# TPS54340_PS_and_Load_Rev1.net
KiCad netlist of a schematic drawn in EAGLE
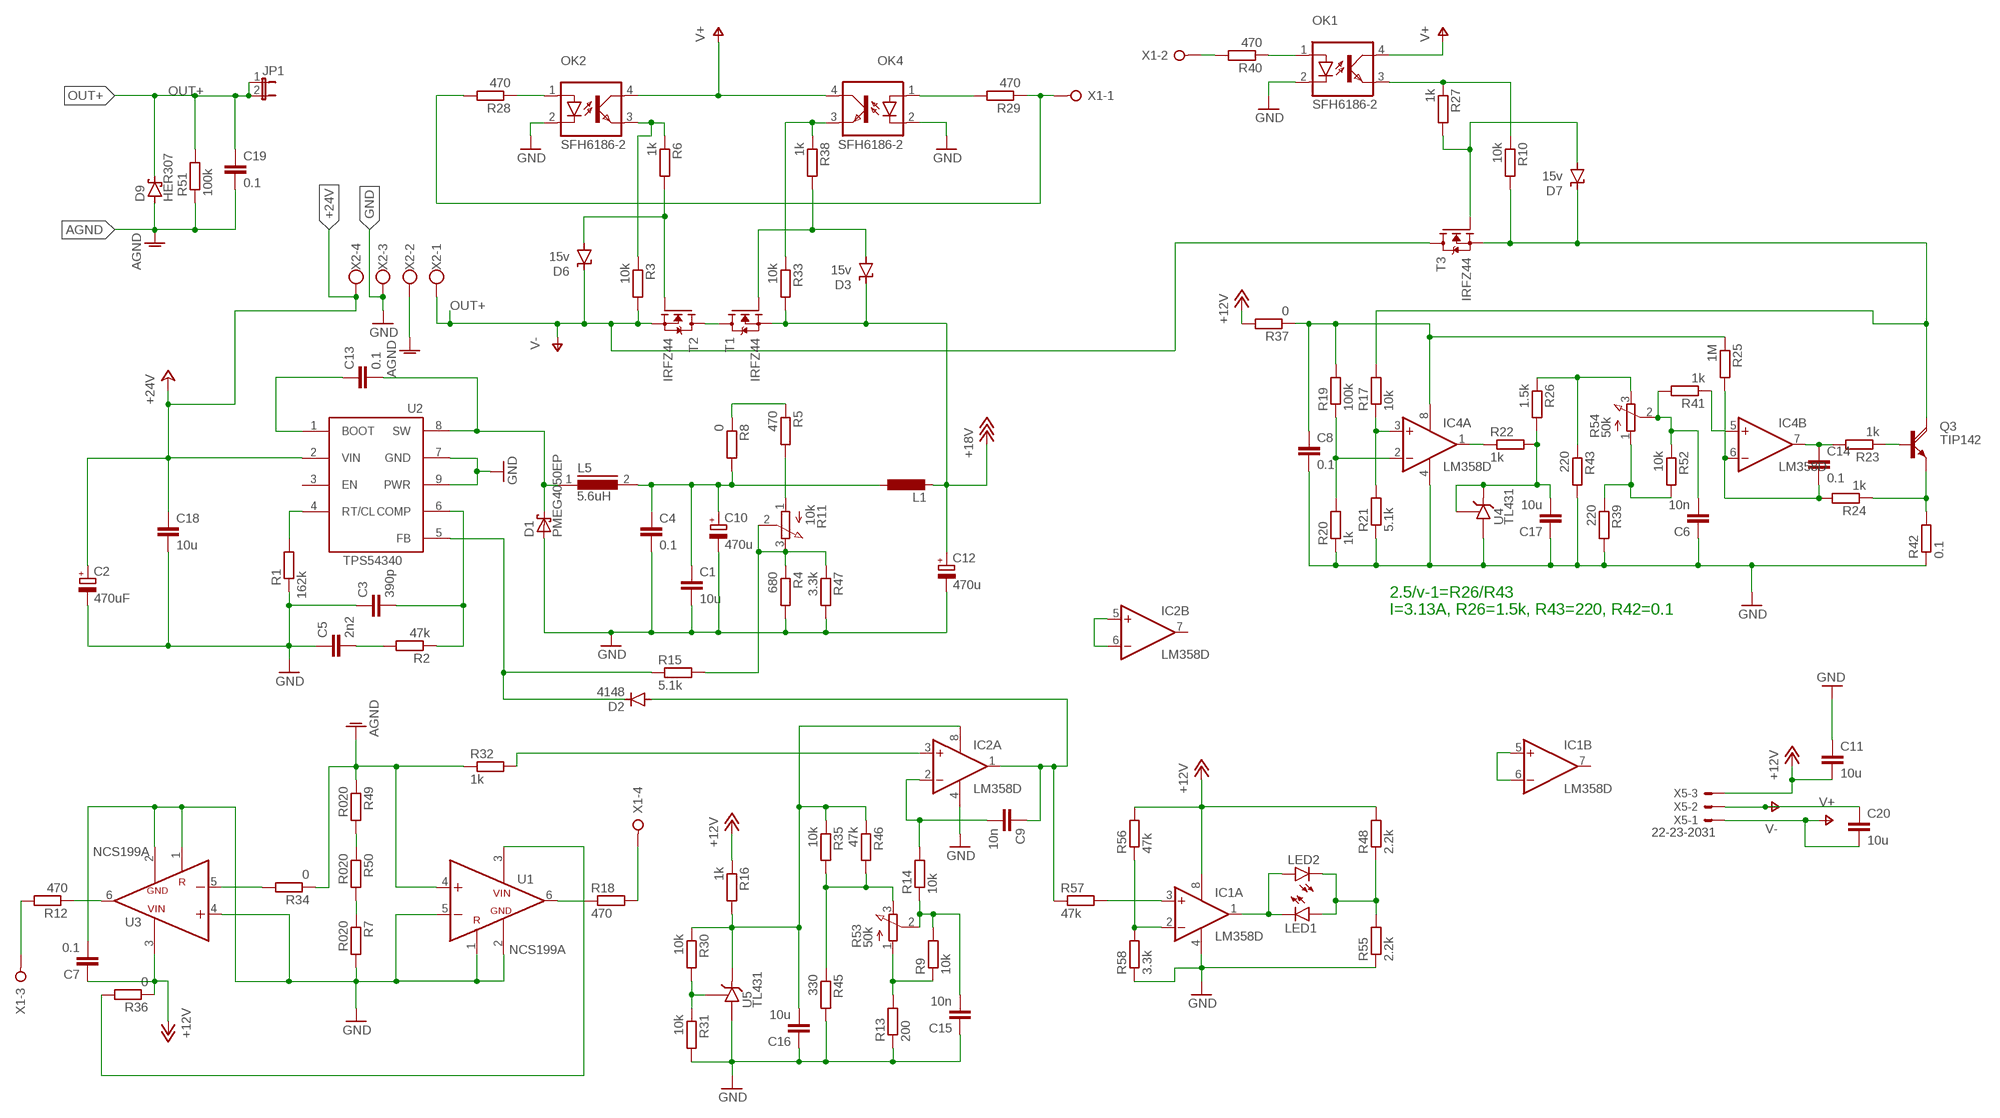
[diagram p0: schematic, sheet 1]

(export (version "E")
  (design (tool "Eeschema 10.0.6"))
  (components
    (comp (ref "C1")
      (value "10u")
      (footprint "eagle-import:C1210")
      (libsource (lib "eagle-import") (part "rcl_334_C-EUC1210"))
    )
    (comp (ref "C2")
      (value "470uF")
      (footprint "eagle-import:E5-10,5")
      (libsource (lib "eagle-import") (part "CPOL-EUE5-10.5"))
    )
    (comp (ref "C3")
      (value "390p")
      (footprint "eagle-import:C0603K")
      (libsource (lib "eagle-import") (part "rcl_334_C-EUC0603K"))
    )
    (comp (ref "C4")
      (value "0.1")
      (footprint "eagle-import:C1206")
      (libsource (lib "eagle-import") (part "C-EUC1206"))
    )
    (comp (ref "C5")
      (value "2n2")
      (footprint "eagle-import:C0603K")
      (libsource (lib "eagle-import") (part "rcl_334_C-EUC0603K"))
    )
    (comp (ref "C6")
      (value "10n")
      (footprint "eagle-import:C0603K")
      (libsource (lib "eagle-import") (part "rcl_334_C-EUC0603K"))
    )
    (comp (ref "C7")
      (value "0.1")
      (footprint "eagle-import:C0603K")
      (libsource (lib "eagle-import") (part "rcl_334_C-EUC0603K"))
    )
    (comp (ref "C8")
      (value "0.1")
      (footprint "eagle-import:C1206")
      (libsource (lib "eagle-import") (part "C-EUC1206"))
    )
    (comp (ref "C9")
      (value "10n")
      (footprint "eagle-import:C0603K")
      (libsource (lib "eagle-import") (part "rcl_334_C-EUC0603K"))
    )
    (comp (ref "C10")
      (value "470u")
      (footprint "eagle-import:E5-10,5")
      (libsource (lib "eagle-import") (part "CPOL-EUE5-10.5"))
    )
    (comp (ref "C11")
      (value "10u")
      (footprint "eagle-import:C1206")
      (libsource (lib "eagle-import") (part "C-EUC1206"))
    )
    (comp (ref "C12")
      (value "470u")
      (footprint "eagle-import:E5-10,5")
      (libsource (lib "eagle-import") (part "CPOL-EUE5-10.5"))
    )
    (comp (ref "C13")
      (value "0.1")
      (footprint "eagle-import:C102-043X133")
      (libsource (lib "eagle-import") (part "rcl_334_C-EU102-043X133"))
    )
    (comp (ref "C14")
      (value "0.1")
      (footprint "eagle-import:C1206")
      (libsource (lib "eagle-import") (part "C-EUC1206"))
    )
    (comp (ref "C15")
      (value "10n")
      (footprint "eagle-import:C0603K")
      (libsource (lib "eagle-import") (part "rcl_334_C-EUC0603K"))
    )
    (comp (ref "C16")
      (value "10u")
      (footprint "eagle-import:C0603K")
      (libsource (lib "eagle-import") (part "rcl_334_C-EUC0603K"))
    )
    (comp (ref "C17")
      (value "10u")
      (footprint "eagle-import:C0603K")
      (libsource (lib "eagle-import") (part "rcl_334_C-EUC0603K"))
    )
    (comp (ref "C18")
      (value "10u")
      (footprint "eagle-import:C1210")
      (libsource (lib "eagle-import") (part "rcl_334_C-EUC1210"))
    )
    (comp (ref "C19")
      (value "0.1")
      (footprint "eagle-import:C150-054X183")
      (libsource (lib "eagle-import") (part "rcl_334_C-EU150-054X183"))
    )
    (comp (ref "C20")
      (value "10u")
      (footprint "eagle-import:C1206")
      (libsource (lib "eagle-import") (part "C-EUC1206"))
    )
    (comp (ref "D1")
      (value "PMEG4050EP")
      (footprint "eagle-import:SOD128")
      (libsource (lib "eagle-import") (part "PMEG4050EP"))
    )
    (comp (ref "D2")
      (value "4148")
      (footprint "eagle-import:SOD80C")
      (libsource (lib "eagle-import") (part "PMLL41SOD80C"))
    )
    (comp (ref "D3")
      (value "15v")
      (footprint "eagle-import:SMBJ")
      (libsource (lib "eagle-import") (part "SUPPRESSOR-SMBJ"))
    )
    (comp (ref "D6")
      (value "15v")
      (footprint "eagle-import:SMBJ")
      (libsource (lib "eagle-import") (part "SUPPRESSOR-SMBJ"))
    )
    (comp (ref "D7")
      (value "15v")
      (footprint "eagle-import:SMBJ")
      (libsource (lib "eagle-import") (part "SUPPRESSOR-SMBJ"))
    )
    (comp (ref "D9")
      (value "HER307")
      (footprint "eagle-import:CB429-17")
      (libsource (lib "eagle-import") (part "15KEXX"))
    )
    (comp (ref "IC1")
      (value "LM358D")
      (footprint "eagle-import:SO08")
      (libsource (lib "eagle-import") (part "LM358D"))
    )
    (comp (ref "IC2")
      (value "LM358D")
      (footprint "eagle-import:SO08")
      (libsource (lib "eagle-import") (part "LM358D"))
    )
    (comp (ref "IC4")
      (value "LM358D")
      (footprint "eagle-import:SO08")
      (libsource (lib "eagle-import") (part "LM358D"))
    )
    (comp (ref "JP1")
      (value "JP1E")
      (footprint "eagle-import:JP1")
      (libsource (lib "eagle-import") (part "JP1E"))
    )
    (comp (ref "L1")
      (value "L-EU0207/5V")
      (footprint "eagle-import:0207_5V")
      (libsource (lib "eagle-import") (part "L-EU0207/5V"))
    )
    (comp (ref "L5")
      (value "5.6uH")
      (footprint "eagle-import:DR125")
      (libsource (lib "eagle-import") (part "DR125"))
    )
    (comp (ref "LED1")
      (value "LEDB152")
      (footprint "eagle-import:Q62902-B152")
      (libsource (lib "eagle-import") (part "LEDB152"))
    )
    (comp (ref "LED2")
      (value "LEDB152")
      (footprint "eagle-import:Q62902-B152")
      (libsource (lib "eagle-import") (part "LEDB152"))
    )
    (comp (ref "OK1")
      (value "SFH6186-2")
      (footprint "eagle-import:SMD4-7")
      (fields (field (name "MF") "VISHAY/TELEFUNKEN"))
      (libsource (lib "eagle-import") (part "SFH618?6-2"))
    )
    (comp (ref "OK2")
      (value "SFH6186-2")
      (footprint "eagle-import:SMD4-7")
      (fields (field (name "MF") "VISHAY/TELEFUNKEN"))
      (libsource (lib "eagle-import") (part "SFH618?6-2"))
    )
    (comp (ref "OK4")
      (value "SFH6186-2")
      (footprint "eagle-import:SMD4-7")
      (fields (field (name "MF") "VISHAY/TELEFUNKEN"))
      (libsource (lib "eagle-import") (part "SFH618?6-2"))
    )
    (comp (ref "Q3")
      (value "TIP142")
      (footprint "eagle-import:SOT93")
      (libsource (lib "eagle-import") (part "TIP142"))
    )
    (comp (ref "R1")
      (value "162k")
      (footprint "eagle-import:R1206")
      (libsource (lib "eagle-import") (part "R-EU_R1206"))
    )
    (comp (ref "R2")
      (value "47k")
      (footprint "eagle-import:R0603")
      (libsource (lib "eagle-import") (part "rcl_334_R-EU_R0603"))
    )
    (comp (ref "R3")
      (value "10k")
      (footprint "eagle-import:R0603")
      (libsource (lib "eagle-import") (part "rcl_334_R-EU_R0603"))
    )
    (comp (ref "R4")
      (value "680")
      (footprint "eagle-import:R1206")
      (libsource (lib "eagle-import") (part "R-EU_R1206"))
    )
    (comp (ref "R5")
      (value "470")
      (footprint "eagle-import:R1206")
      (libsource (lib "eagle-import") (part "R-EU_R1206"))
    )
    (comp (ref "R6")
      (value "1k")
      (footprint "eagle-import:R0603")
      (libsource (lib "eagle-import") (part "rcl_334_R-EU_R0603"))
    )
    (comp (ref "R7")
      (value "R020")
      (footprint "eagle-import:R1206")
      (libsource (lib "eagle-import") (part "R-EU_R1206"))
    )
    (comp (ref "R8")
      (value "0")
      (footprint "eagle-import:R0603")
      (libsource (lib "eagle-import") (part "rcl_334_R-EU_R0603"))
    )
    (comp (ref "R9")
      (value "10k")
      (footprint "eagle-import:R0603")
      (libsource (lib "eagle-import") (part "rcl_334_R-EU_R0603"))
    )
    (comp (ref "R10")
      (value "10k")
      (footprint "eagle-import:R0603")
      (libsource (lib "eagle-import") (part "rcl_334_R-EU_R0603"))
    )
    (comp (ref "R11")
      (value "10k")
      (footprint "eagle-import:3RP_1610N")
      (libsource (lib "eagle-import") (part "3RP/1610N"))
    )
    (comp (ref "R12")
      (value "470")
      (footprint "eagle-import:R0603")
      (libsource (lib "eagle-import") (part "rcl_334_R-EU_R0603"))
    )
    (comp (ref "R13")
      (value "200")
      (footprint "eagle-import:R0603")
      (libsource (lib "eagle-import") (part "rcl_334_R-EU_R0603"))
    )
    (comp (ref "R14")
      (value "10k")
      (footprint "eagle-import:R1206")
      (libsource (lib "eagle-import") (part "R-EU_R1206"))
    )
    (comp (ref "R15")
      (value "5.1k")
      (footprint "eagle-import:R0603")
      (libsource (lib "eagle-import") (part "rcl_334_R-EU_R0603"))
    )
    (comp (ref "R16")
      (value "1k")
      (footprint "eagle-import:R0603")
      (libsource (lib "eagle-import") (part "rcl_334_R-EU_R0603"))
    )
    (comp (ref "R17")
      (value "10k")
      (footprint "eagle-import:R1206")
      (libsource (lib "eagle-import") (part "R-EU_R1206"))
    )
    (comp (ref "R18")
      (value "470")
      (footprint "eagle-import:R0603")
      (libsource (lib "eagle-import") (part "rcl_334_R-EU_R0603"))
    )
    (comp (ref "R19")
      (value "100k")
      (footprint "eagle-import:R1206")
      (libsource (lib "eagle-import") (part "R-EU_R1206"))
    )
    (comp (ref "R20")
      (value "1k")
      (footprint "eagle-import:R1206")
      (libsource (lib "eagle-import") (part "R-EU_R1206"))
    )
    (comp (ref "R21")
      (value "5.1k")
      (footprint "eagle-import:R1206")
      (libsource (lib "eagle-import") (part "R-EU_R1206"))
    )
    (comp (ref "R22")
      (value "1k")
      (footprint "eagle-import:R0603")
      (libsource (lib "eagle-import") (part "rcl_334_R-EU_R0603"))
    )
    (comp (ref "R23")
      (value "1k")
      (footprint "eagle-import:R1206")
      (libsource (lib "eagle-import") (part "R-EU_R1206"))
    )
    (comp (ref "R24")
      (value "1k")
      (footprint "eagle-import:R1206")
      (libsource (lib "eagle-import") (part "R-EU_R1206"))
    )
    (comp (ref "R25")
      (value "1M")
      (footprint "eagle-import:R1206")
      (libsource (lib "eagle-import") (part "R-EU_R1206"))
    )
    (comp (ref "R26")
      (value "1.5k")
      (footprint "eagle-import:R0603")
      (libsource (lib "eagle-import") (part "rcl_334_R-EU_R0603"))
    )
    (comp (ref "R27")
      (value "1k")
      (footprint "eagle-import:R0603")
      (libsource (lib "eagle-import") (part "rcl_334_R-EU_R0603"))
    )
    (comp (ref "R28")
      (value "470")
      (footprint "eagle-import:R0603")
      (libsource (lib "eagle-import") (part "rcl_334_R-EU_R0603"))
    )
    (comp (ref "R29")
      (value "470")
      (footprint "eagle-import:R0603")
      (libsource (lib "eagle-import") (part "rcl_334_R-EU_R0603"))
    )
    (comp (ref "R30")
      (value "10k")
      (footprint "eagle-import:R0603")
      (libsource (lib "eagle-import") (part "rcl_334_R-EU_R0603"))
    )
    (comp (ref "R31")
      (value "10k")
      (footprint "eagle-import:R0603")
      (libsource (lib "eagle-import") (part "rcl_334_R-EU_R0603"))
    )
    (comp (ref "R32")
      (value "1k")
      (footprint "eagle-import:R1206")
      (libsource (lib "eagle-import") (part "R-EU_R1206"))
    )
    (comp (ref "R33")
      (value "10k")
      (footprint "eagle-import:R0603")
      (libsource (lib "eagle-import") (part "rcl_334_R-EU_R0603"))
    )
    (comp (ref "R34")
      (value "0")
      (footprint "eagle-import:R1206")
      (libsource (lib "eagle-import") (part "R-EU_R1206"))
    )
    (comp (ref "R35")
      (value "10k")
      (footprint "eagle-import:R0603")
      (libsource (lib "eagle-import") (part "rcl_334_R-EU_R0603"))
    )
    (comp (ref "R36")
      (value "0")
      (footprint "eagle-import:R1206")
      (libsource (lib "eagle-import") (part "R-EU_R1206"))
    )
    (comp (ref "R37")
      (value "0")
      (footprint "eagle-import:R1206")
      (libsource (lib "eagle-import") (part "R-EU_R1206"))
    )
    (comp (ref "R38")
      (value "1k")
      (footprint "eagle-import:R0603")
      (libsource (lib "eagle-import") (part "rcl_334_R-EU_R0603"))
    )
    (comp (ref "R39")
      (value "220")
      (footprint "eagle-import:R0603")
      (libsource (lib "eagle-import") (part "rcl_334_R-EU_R0603"))
    )
    (comp (ref "R40")
      (value "470")
      (footprint "eagle-import:R0603")
      (libsource (lib "eagle-import") (part "rcl_334_R-EU_R0603"))
    )
    (comp (ref "R41")
      (value "1k")
      (footprint "eagle-import:R1206")
      (libsource (lib "eagle-import") (part "R-EU_R1206"))
    )
    (comp (ref "R42")
      (value "0.1")
      (footprint "eagle-import:0414_15")
      (libsource (lib "eagle-import") (part "rcl_334_R-EU_0414/15"))
    )
    (comp (ref "R43")
      (value "220")
      (footprint "eagle-import:R0603")
      (libsource (lib "eagle-import") (part "rcl_334_R-EU_R0603"))
    )
    (comp (ref "R45")
      (value "330")
      (footprint "eagle-import:R0603")
      (libsource (lib "eagle-import") (part "rcl_334_R-EU_R0603"))
    )
    (comp (ref "R46")
      (value "47k")
      (footprint "eagle-import:R0603")
      (libsource (lib "eagle-import") (part "rcl_334_R-EU_R0603"))
    )
    (comp (ref "R47")
      (value "3.3k")
      (footprint "eagle-import:R1206")
      (libsource (lib "eagle-import") (part "R-EU_R1206"))
    )
    (comp (ref "R48")
      (value "2.2k")
      (footprint "eagle-import:R0603")
      (libsource (lib "eagle-import") (part "rcl_334_R-EU_R0603"))
    )
    (comp (ref "R49")
      (value "R020")
      (footprint "eagle-import:R1206")
      (libsource (lib "eagle-import") (part "R-EU_R1206"))
    )
    (comp (ref "R50")
      (value "R020")
      (footprint "eagle-import:R1206")
      (libsource (lib "eagle-import") (part "R-EU_R1206"))
    )
    (comp (ref "R51")
      (value "100k")
      (footprint "eagle-import:0207_15")
      (libsource (lib "eagle-import") (part "rcl_334_R-EU_0207/15"))
    )
    (comp (ref "R52")
      (value "10k")
      (footprint "eagle-import:R0603")
      (libsource (lib "eagle-import") (part "rcl_334_R-EU_R0603"))
    )
    (comp (ref "R53")
      (value "50k")
      (footprint "eagle-import:3RP_1610N")
      (libsource (lib "eagle-import") (part "3RP/1610N"))
    )
    (comp (ref "R54")
      (value "50k")
      (footprint "eagle-import:3RP_1610N")
      (libsource (lib "eagle-import") (part "3RP/1610N"))
    )
    (comp (ref "R55")
      (value "2.2k")
      (footprint "eagle-import:R0603")
      (libsource (lib "eagle-import") (part "rcl_334_R-EU_R0603"))
    )
    (comp (ref "R56")
      (value "47k")
      (footprint "eagle-import:R0603")
      (libsource (lib "eagle-import") (part "rcl_334_R-EU_R0603"))
    )
    (comp (ref "R57")
      (value "47k")
      (footprint "eagle-import:R0603")
      (libsource (lib "eagle-import") (part "rcl_334_R-EU_R0603"))
    )
    (comp (ref "R58")
      (value "3.3k")
      (footprint "eagle-import:R0603")
      (libsource (lib "eagle-import") (part "rcl_334_R-EU_R0603"))
    )
    (comp (ref "T1")
      (value "IRFZ44")
      (footprint "eagle-import:DPAK_TO252")
      (libsource (lib "eagle-import") (part "MOSFET-N-DPAK"))
    )
    (comp (ref "T2")
      (value "IRFZ44")
      (footprint "eagle-import:DPAK_TO252")
      (libsource (lib "eagle-import") (part "MOSFET-N-DPAK"))
    )
    (comp (ref "T3")
      (value "IRFZ44")
      (footprint "eagle-import:DPAK_TO252")
      (libsource (lib "eagle-import") (part "MOSFET-N-DPAK"))
    )
    (comp (ref "U1")
      (value "NCS199A")
      (footprint "eagle-import:SOT363")
      (libsource (lib "eagle-import") (part "NCS199A"))
    )
    (comp (ref "U2")
      (value "TPS54340")
      (footprint "eagle-import:HSOP")
      (libsource (lib "eagle-import") (part "TPS54340SO8"))
    )
    (comp (ref "U3")
      (value "NCS199A")
      (footprint "eagle-import:SOT363")
      (libsource (lib "eagle-import") (part "NCS199A"))
    )
    (comp (ref "U4")
      (value "TL431")
      (footprint "eagle-import:SOT23")
      (libsource (lib "eagle-import") (part "TL431"))
    )
    (comp (ref "U5")
      (value "TL431")
      (footprint "eagle-import:SOT23")
      (libsource (lib "eagle-import") (part "TL431"))
    )
    (comp (ref "X1")
      (value "W237-04P")
      (footprint "eagle-import:W237-4P")
      (libsource (lib "eagle-import") (part "W237-04P"))
    )
    (comp (ref "X2")
      (value "W237-4")
      (footprint "eagle-import:W237-4")
      (libsource (lib "eagle-import") (part "W237-4"))
    )
    (comp (ref "X5")
      (value "22-23-2031")
      (footprint "eagle-import:22-23-2031")
      (fields (field (name "MF") "MOLEX"))
      (libsource (lib "eagle-import") (part "22-23-2031"))
    )
  )
  (nets
    (net (code "1") (name "+12V") (class "Default")
      (node (ref "C11") (pin "2") (pinfunction "2_2") (pintype "passive"))
      (node (ref "C7") (pin "1") (pinfunction "1_1") (pintype "passive"))
      (node (ref "IC1") (pin "8") (pinfunction "V+_8") (pintype "power_in"))
      (node (ref "R16") (pin "1") (pinfunction "1_1") (pintype "passive"))
      (node (ref "R36") (pin "1") (pinfunction "1_1") (pintype "passive"))
      (node (ref "R37") (pin "2") (pinfunction "2_2") (pintype "passive"))
      (node (ref "R48") (pin "2") (pinfunction "2_2") (pintype "passive"))
      (node (ref "R56") (pin "2") (pinfunction "2_2") (pintype "passive"))
      (node (ref "U3") (pin "3") (pinfunction "VCC_3") (pintype "power_in"))
      (node (ref "X5") (pin "3") (pinfunction "S_3") (pintype "passive"))
    )
    (net (code "2") (name "+18V") (class "Default")
      (node (ref "C12") (pin "+") (pinfunction "+_+") (pintype "passive"))
      (node (ref "D3") (pin "C") (pinfunction "C_C") (pintype "passive"))
      (node (ref "L1") (pin "2") (pinfunction "2_2") (pintype "passive"))
      (node (ref "R33") (pin "2") (pinfunction "2_2") (pintype "passive"))
      (node (ref "T1") (pin "3") (pinfunction "S_3") (pintype "passive"))
    )
    (net (code "3") (name "+24V") (class "Default")
      (node (ref "C18") (pin "1") (pinfunction "1_1") (pintype "passive"))
      (node (ref "C2") (pin "+") (pinfunction "+_+") (pintype "passive"))
      (node (ref "U2") (pin "2") (pinfunction "VIN_2") (pintype "power_in"))
      (node (ref "X2") (pin "4") (pinfunction "KL_4") (pintype "passive"))
    )
    (net (code "4") (name "AGND") (class "Default")
      (node (ref "C19") (pin "2") (pinfunction "2_2") (pintype "passive"))
      (node (ref "D9") (pin "A") (pinfunction "A_A") (pintype "passive"))
      (node (ref "R32") (pin "1") (pinfunction "1_1") (pintype "passive"))
      (node (ref "R34") (pin "1") (pinfunction "1_1") (pintype "passive"))
      (node (ref "R49") (pin "1") (pinfunction "1_1") (pintype "passive"))
      (node (ref "R51") (pin "1") (pinfunction "1_1") (pintype "passive"))
      (node (ref "U1") (pin "4") (pinfunction "IN+_4") (pintype "input"))
      (node (ref "X2") (pin "2") (pinfunction "KL_2") (pintype "passive"))
    )
    (net (code "5") (name "GND") (class "Default")
      (node (ref "C1") (pin "2") (pinfunction "2_2") (pintype "passive"))
      (node (ref "C10") (pin "-") (pinfunction "-_-") (pintype "passive"))
      (node (ref "C11") (pin "1") (pinfunction "1_1") (pintype "passive"))
      (node (ref "C12") (pin "-") (pinfunction "-_-") (pintype "passive"))
      (node (ref "C15") (pin "1") (pinfunction "1_1") (pintype "passive"))
      (node (ref "C16") (pin "1") (pinfunction "1_1") (pintype "passive"))
      (node (ref "C17") (pin "1") (pinfunction "1_1") (pintype "passive"))
      (node (ref "C18") (pin "2") (pinfunction "2_2") (pintype "passive"))
      (node (ref "C2") (pin "-") (pinfunction "-_-") (pintype "passive"))
      (node (ref "C3") (pin "1") (pinfunction "1_1") (pintype "passive"))
      (node (ref "C4") (pin "2") (pinfunction "2_2") (pintype "passive"))
      (node (ref "C5") (pin "1") (pinfunction "1_1") (pintype "passive"))
      (node (ref "C6") (pin "1") (pinfunction "1_1") (pintype "passive"))
      (node (ref "C7") (pin "2") (pinfunction "2_2") (pintype "passive"))
      (node (ref "C8") (pin "2") (pinfunction "2_2") (pintype "passive"))
      (node (ref "D1") (pin "2") (pinfunction "A_2") (pintype "passive"))
      (node (ref "IC1") (pin "4") (pinfunction "V-_4") (pintype "power_in"))
      (node (ref "IC2") (pin "4") (pinfunction "V-_4") (pintype "power_in"))
      (node (ref "IC4") (pin "4") (pinfunction "V-_4") (pintype "power_in"))
      (node (ref "OK1") (pin "2") (pinfunction "C_2") (pintype "passive"))
      (node (ref "OK2") (pin "2") (pinfunction "C_2") (pintype "passive"))
      (node (ref "OK4") (pin "2") (pinfunction "C_2") (pintype "passive"))
      (node (ref "R1") (pin "1") (pinfunction "1_1") (pintype "passive"))
      (node (ref "R13") (pin "1") (pinfunction "1_1") (pintype "passive"))
      (node (ref "R20") (pin "1") (pinfunction "1_1") (pintype "passive"))
      (node (ref "R21") (pin "1") (pinfunction "1_1") (pintype "passive"))
      (node (ref "R31") (pin "2") (pinfunction "2_2") (pintype "passive"))
      (node (ref "R39") (pin "2") (pinfunction "2_2") (pintype "passive"))
      (node (ref "R4") (pin "2") (pinfunction "2_2") (pintype "passive"))
      (node (ref "R42") (pin "1") (pinfunction "1_1") (pintype "passive"))
      (node (ref "R43") (pin "2") (pinfunction "2_2") (pintype "passive"))
      (node (ref "R45") (pin "2") (pinfunction "2_2") (pintype "passive"))
      (node (ref "R47") (pin "2") (pinfunction "2_2") (pintype "passive"))
      (node (ref "R55") (pin "1") (pinfunction "1_1") (pintype "passive"))
      (node (ref "R58") (pin "1") (pinfunction "1_1") (pintype "passive"))
      (node (ref "R7") (pin "2") (pinfunction "2_2") (pintype "passive"))
      (node (ref "U1") (pin "1") (pinfunction "REF_1") (pintype "input"))
      (node (ref "U1") (pin "2") (pinfunction "GND_2") (pintype "power_in"))
      (node (ref "U1") (pin "5") (pinfunction "IN-_5") (pintype "input"))
      (node (ref "U2") (pin "7") (pinfunction "GND_7") (pintype "power_in"))
      (node (ref "U2") (pin "9") (pinfunction "PWR_9") (pintype "power_in"))
      (node (ref "U3") (pin "1") (pinfunction "REF_1") (pintype "input"))
      (node (ref "U3") (pin "2") (pinfunction "GND_2") (pintype "power_in"))
      (node (ref "U3") (pin "4") (pinfunction "IN+_4") (pintype "input"))
      (node (ref "U4") (pin "3") (pinfunction "A_3") (pintype "passive"))
      (node (ref "U5") (pin "3") (pinfunction "A_3") (pintype "passive"))
      (node (ref "X2") (pin "3") (pinfunction "KL_3") (pintype "passive"))
    )
    (net (code "6") (name "Net-(C1-Pad1)") (class "Default")
      (node (ref "C1") (pin "1") (pinfunction "1_1") (pintype "passive"))
      (node (ref "C10") (pin "+") (pinfunction "+_+") (pintype "passive"))
      (node (ref "C4") (pin "1") (pinfunction "1_1") (pintype "passive"))
      (node (ref "L1") (pin "1") (pinfunction "1_1") (pintype "passive"))
      (node (ref "L5") (pin "2") (pinfunction "2_2") (pintype "passive"))
      (node (ref "R8") (pin "2") (pinfunction "2_2") (pintype "passive"))
    )
    (net (code "7") (name "Net-(C5-Pad2)") (class "Default")
      (node (ref "C5") (pin "2") (pinfunction "2_2") (pintype "passive"))
      (node (ref "R2") (pin "2") (pinfunction "2_2") (pintype "passive"))
    )
    (net (code "8") (name "Net-(D1-K)") (class "Default")
      (node (ref "C13") (pin "2") (pinfunction "2_2") (pintype "passive"))
      (node (ref "D1") (pin "1") (pinfunction "K_1") (pintype "passive"))
      (node (ref "L5") (pin "1") (pinfunction "1_1") (pintype "passive"))
      (node (ref "U2") (pin "8") (pinfunction "SW_8") (pintype "power_in"))
    )
    (net (code "9") (name "Net-(IC1A-+IN)") (class "Default")
      (node (ref "IC1") (pin "3") (pinfunction "+IN_3") (pintype "input"))
      (node (ref "R57") (pin "2") (pinfunction "2_2") (pintype "passive"))
    )
    (net (code "10") (name "Net-(IC1A--IN)") (class "Default")
      (node (ref "IC1") (pin "2") (pinfunction "-IN_2") (pintype "input"))
      (node (ref "R56") (pin "1") (pinfunction "1_1") (pintype "passive"))
      (node (ref "R58") (pin "2") (pinfunction "2_2") (pintype "passive"))
    )
    (net (code "11") (name "Net-(IC1A-OUT)") (class "Default")
      (node (ref "IC1") (pin "1") (pinfunction "OUT_1") (pintype "output"))
      (node (ref "LED1") (pin "K") (pinfunction "C_K") (pintype "passive"))
      (node (ref "LED2") (pin "A") (pinfunction "A_A") (pintype "passive"))
    )
    (net (code "12") (name "Net-(IC1B-+IN)") (class "Default")
      (node (ref "IC1") (pin "5") (pinfunction "+IN_5") (pintype "input"))
      (node (ref "IC1") (pin "6") (pinfunction "-IN_6") (pintype "input"))
    )
    (net (code "13") (name "Net-(IC2A-+IN)") (class "Default")
      (node (ref "IC2") (pin "3") (pinfunction "+IN_3") (pintype "input"))
      (node (ref "R32") (pin "2") (pinfunction "2_2") (pintype "passive"))
    )
    (net (code "14") (name "Net-(IC2A--IN)") (class "Default")
      (node (ref "C9") (pin "2") (pinfunction "2_2") (pintype "passive"))
      (node (ref "IC2") (pin "2") (pinfunction "-IN_2") (pintype "input"))
      (node (ref "R14") (pin "2") (pinfunction "2_2") (pintype "passive"))
    )
    (net (code "15") (name "Net-(IC2A-OUT)") (class "Default")
      (node (ref "C9") (pin "1") (pinfunction "1_1") (pintype "passive"))
      (node (ref "D2") (pin "A") (pinfunction "A_A") (pintype "passive"))
      (node (ref "IC2") (pin "1") (pinfunction "OUT_1") (pintype "output"))
      (node (ref "R57") (pin "1") (pinfunction "1_1") (pintype "passive"))
    )
    (net (code "16") (name "Net-(IC2B-+IN)") (class "Default")
      (node (ref "IC2") (pin "5") (pinfunction "+IN_5") (pintype "input"))
      (node (ref "IC2") (pin "6") (pinfunction "-IN_6") (pintype "input"))
    )
    (net (code "17") (name "Net-(IC2C-V+)") (class "Default")
      (node (ref "C16") (pin "2") (pinfunction "2_2") (pintype "passive"))
      (node (ref "IC2") (pin "8") (pinfunction "V+_8") (pintype "power_in"))
      (node (ref "R16") (pin "2") (pinfunction "2_2") (pintype "passive"))
      (node (ref "R30") (pin "1") (pinfunction "1_1") (pintype "passive"))
      (node (ref "R35") (pin "1") (pinfunction "1_1") (pintype "passive"))
      (node (ref "R46") (pin "1") (pinfunction "1_1") (pintype "passive"))
      (node (ref "U5") (pin "1") (pinfunction "C_1") (pintype "passive"))
    )
    (net (code "18") (name "Net-(IC4A-+IN)") (class "Default")
      (node (ref "IC4") (pin "3") (pinfunction "+IN_3") (pintype "input"))
      (node (ref "R17") (pin "1") (pinfunction "1_1") (pintype "passive"))
      (node (ref "R21") (pin "2") (pinfunction "2_2") (pintype "passive"))
    )
    (net (code "19") (name "Net-(IC4A--IN)") (class "Default")
      (node (ref "IC4") (pin "2") (pinfunction "-IN_2") (pintype "input"))
      (node (ref "R19") (pin "1") (pinfunction "1_1") (pintype "passive"))
      (node (ref "R20") (pin "2") (pinfunction "2_2") (pintype "passive"))
    )
    (net (code "20") (name "Net-(IC4A-OUT)") (class "Default")
      (node (ref "IC4") (pin "1") (pinfunction "OUT_1") (pintype "output"))
      (node (ref "R22") (pin "1") (pinfunction "1_1") (pintype "passive"))
    )
    (net (code "21") (name "Net-(IC4B-+IN)") (class "Default")
      (node (ref "IC4") (pin "5") (pinfunction "+IN_5") (pintype "input"))
      (node (ref "R41") (pin "1") (pinfunction "1_1") (pintype "passive"))
    )
    (net (code "22") (name "Net-(IC4B--IN)") (class "Default")
      (node (ref "C14") (pin "2") (pinfunction "2_2") (pintype "passive"))
      (node (ref "IC4") (pin "6") (pinfunction "-IN_6") (pintype "input"))
      (node (ref "R24") (pin "2") (pinfunction "2_2") (pintype "passive"))
      (node (ref "R25") (pin "2") (pinfunction "2_2") (pintype "passive"))
    )
    (net (code "23") (name "Net-(IC4B-OUT)") (class "Default")
      (node (ref "C14") (pin "1") (pinfunction "1_1") (pintype "passive"))
      (node (ref "IC4") (pin "7") (pinfunction "OUT_7") (pintype "output"))
      (node (ref "R23") (pin "2") (pinfunction "2_2") (pintype "passive"))
    )
    (net (code "24") (name "Net-(IC4C-V+)") (class "Default")
      (node (ref "C8") (pin "1") (pinfunction "1_1") (pintype "passive"))
      (node (ref "IC4") (pin "8") (pinfunction "V+_8") (pintype "power_in"))
      (node (ref "R19") (pin "2") (pinfunction "2_2") (pintype "passive"))
      (node (ref "R25") (pin "1") (pinfunction "1_1") (pintype "passive"))
      (node (ref "R37") (pin "1") (pinfunction "1_1") (pintype "passive"))
    )
    (net (code "25") (name "Net-(LED2-C)") (class "Default")
      (node (ref "LED1") (pin "A") (pinfunction "A_A") (pintype "passive"))
      (node (ref "LED2") (pin "K") (pinfunction "C_K") (pintype "passive"))
      (node (ref "R48") (pin "1") (pinfunction "1_1") (pintype "passive"))
      (node (ref "R55") (pin "2") (pinfunction "2_2") (pintype "passive"))
    )
    (net (code "26") (name "Net-(OK1-A)") (class "Default")
      (node (ref "OK1") (pin "1") (pinfunction "A_1") (pintype "passive"))
      (node (ref "R40") (pin "1") (pinfunction "1_1") (pintype "passive"))
    )
    (net (code "27") (name "Net-(OK1-EMIT)") (class "Default")
      (node (ref "OK1") (pin "3") (pinfunction "EMIT_3") (pintype "passive"))
      (node (ref "R10") (pin "1") (pinfunction "1_1") (pintype "passive"))
      (node (ref "R27") (pin "1") (pinfunction "1_1") (pintype "passive"))
    )
    (net (code "28") (name "Net-(OK2-A)") (class "Default")
      (node (ref "OK2") (pin "1") (pinfunction "A_1") (pintype "passive"))
      (node (ref "R28") (pin "1") (pinfunction "1_1") (pintype "passive"))
    )
    (net (code "29") (name "Net-(OK2-EMIT)") (class "Default")
      (node (ref "OK2") (pin "3") (pinfunction "EMIT_3") (pintype "passive"))
      (node (ref "R3") (pin "1") (pinfunction "1_1") (pintype "passive"))
      (node (ref "R6") (pin "1") (pinfunction "1_1") (pintype "passive"))
    )
    (net (code "30") (name "Net-(OK4-A)") (class "Default")
      (node (ref "OK4") (pin "1") (pinfunction "A_1") (pintype "passive"))
      (node (ref "R29") (pin "2") (pinfunction "2_2") (pintype "passive"))
    )
    (net (code "31") (name "Net-(OK4-EMIT)") (class "Default")
      (node (ref "OK4") (pin "3") (pinfunction "EMIT_3") (pintype "passive"))
      (node (ref "R33") (pin "1") (pinfunction "1_1") (pintype "passive"))
      (node (ref "R38") (pin "1") (pinfunction "1_1") (pintype "passive"))
    )
    (net (code "32") (name "Net-(Q3-PadB)") (class "Default")
      (node (ref "Q3") (pin "B") (pinfunction "B_B") (pintype "passive"))
      (node (ref "R23") (pin "1") (pinfunction "1_1") (pintype "passive"))
    )
    (net (code "33") (name "Net-(Q3-PadE)") (class "Default")
      (node (ref "Q3") (pin "E") (pinfunction "E_E") (pintype "passive"))
      (node (ref "R24") (pin "1") (pinfunction "1_1") (pintype "passive"))
      (node (ref "R42") (pin "2") (pinfunction "2_2") (pintype "passive"))
    )
    (net (code "34") (name "Net-(R5-Pad1)") (class "Default")
      (node (ref "R5") (pin "1") (pinfunction "1_1") (pintype "passive"))
      (node (ref "R8") (pin "1") (pinfunction "1_1") (pintype "passive"))
    )
    (net (code "35") (name "Net-(R11-A)") (class "Default")
      (node (ref "R11") (pin "1") (pinfunction "A_1") (pintype "passive"))
      (node (ref "R5") (pin "2") (pinfunction "2_2") (pintype "passive"))
    )
    (net (code "36") (name "Net-(R11-E)") (class "Default")
      (node (ref "R11") (pin "2") (pinfunction "S_2") (pintype "passive"))
      (node (ref "R11") (pin "3") (pinfunction "E_3") (pintype "passive"))
      (node (ref "R15") (pin "2") (pinfunction "2_2") (pintype "passive"))
      (node (ref "R4") (pin "1") (pinfunction "1_1") (pintype "passive"))
      (node (ref "R47") (pin "1") (pinfunction "1_1") (pintype "passive"))
    )
    (net (code "37") (name "Net-(R49-Pad2)") (class "Default")
      (node (ref "R49") (pin "2") (pinfunction "2_2") (pintype "passive"))
      (node (ref "R50") (pin "1") (pinfunction "1_1") (pintype "passive"))
    )
    (net (code "38") (name "Net-(R50-Pad2)") (class "Default")
      (node (ref "R50") (pin "2") (pinfunction "2_2") (pintype "passive"))
      (node (ref "R7") (pin "1") (pinfunction "1_1") (pintype "passive"))
    )
    (net (code "39") (name "Net-(R53-A)") (class "Default")
      (node (ref "R13") (pin "2") (pinfunction "2_2") (pintype "passive"))
      (node (ref "R53") (pin "1") (pinfunction "A_1") (pintype "passive"))
      (node (ref "R9") (pin "1") (pinfunction "1_1") (pintype "passive"))
    )
    (net (code "40") (name "Net-(R53-E)") (class "Default")
      (node (ref "R35") (pin "2") (pinfunction "2_2") (pintype "passive"))
      (node (ref "R45") (pin "1") (pinfunction "1_1") (pintype "passive"))
      (node (ref "R46") (pin "2") (pinfunction "2_2") (pintype "passive"))
      (node (ref "R53") (pin "3") (pinfunction "E_3") (pintype "passive"))
    )
    (net (code "41") (name "Net-(R53-S)") (class "Default")
      (node (ref "C15") (pin "2") (pinfunction "2_2") (pintype "passive"))
      (node (ref "R14") (pin "1") (pinfunction "1_1") (pintype "passive"))
      (node (ref "R53") (pin "2") (pinfunction "S_2") (pintype "passive"))
      (node (ref "R9") (pin "2") (pinfunction "2_2") (pintype "passive"))
    )
    (net (code "42") (name "Net-(R54-A)") (class "Default")
      (node (ref "R39") (pin "1") (pinfunction "1_1") (pintype "passive"))
      (node (ref "R52") (pin "2") (pinfunction "2_2") (pintype "passive"))
      (node (ref "R54") (pin "1") (pinfunction "A_1") (pintype "passive"))
    )
    (net (code "43") (name "Net-(R54-E)") (class "Default")
      (node (ref "R26") (pin "1") (pinfunction "1_1") (pintype "passive"))
      (node (ref "R43") (pin "1") (pinfunction "1_1") (pintype "passive"))
      (node (ref "R54") (pin "3") (pinfunction "E_3") (pintype "passive"))
    )
    (net (code "44") (name "Net-(R54-S)") (class "Default")
      (node (ref "C6") (pin "2") (pinfunction "2_2") (pintype "passive"))
      (node (ref "R41") (pin "2") (pinfunction "2_2") (pintype "passive"))
      (node (ref "R52") (pin "1") (pinfunction "1_1") (pintype "passive"))
      (node (ref "R54") (pin "2") (pinfunction "S_2") (pintype "passive"))
    )
    (net (code "45") (name "Net-(T1-D)") (class "Default")
      (node (ref "T1") (pin "2") (pinfunction "D_2") (pintype "passive"))
      (node (ref "T2") (pin "2") (pinfunction "D_2") (pintype "passive"))
    )
    (net (code "46") (name "Net-(T1-G)") (class "Default")
      (node (ref "D3") (pin "A") (pinfunction "A_A") (pintype "passive"))
      (node (ref "R38") (pin "2") (pinfunction "2_2") (pintype "passive"))
      (node (ref "T1") (pin "1") (pinfunction "G_1") (pintype "passive"))
    )
    (net (code "47") (name "Net-(T2-G)") (class "Default")
      (node (ref "D6") (pin "A") (pinfunction "A_A") (pintype "passive"))
      (node (ref "R6") (pin "2") (pinfunction "2_2") (pintype "passive"))
      (node (ref "T2") (pin "1") (pinfunction "G_1") (pintype "passive"))
    )
    (net (code "48") (name "Net-(T3-G)") (class "Default")
      (node (ref "D7") (pin "A") (pinfunction "A_A") (pintype "passive"))
      (node (ref "R27") (pin "2") (pinfunction "2_2") (pintype "passive"))
      (node (ref "T3") (pin "1") (pinfunction "G_1") (pintype "passive"))
    )
    (net (code "49") (name "Net-(T3-S)") (class "Default")
      (node (ref "D7") (pin "C") (pinfunction "C_C") (pintype "passive"))
      (node (ref "Q3") (pin "C") (pinfunction "C_C") (pintype "passive"))
      (node (ref "R10") (pin "2") (pinfunction "2_2") (pintype "passive"))
      (node (ref "R17") (pin "2") (pinfunction "2_2") (pintype "passive"))
      (node (ref "T3") (pin "3") (pinfunction "S_3") (pintype "passive"))
    )
    (net (code "50") (name "Net-(U1-OUT)") (class "Default")
      (node (ref "R18") (pin "1") (pinfunction "1_1") (pintype "passive"))
      (node (ref "U1") (pin "6") (pinfunction "OUT_6") (pintype "output"))
    )
    (net (code "51") (name "Net-(U1-VCC)") (class "Default")
      (node (ref "R36") (pin "2") (pinfunction "2_2") (pintype "passive"))
      (node (ref "U1") (pin "3") (pinfunction "VCC_3") (pintype "power_in"))
    )
    (net (code "52") (name "Net-(U2-BOOT)") (class "Default")
      (node (ref "C13") (pin "1") (pinfunction "1_1") (pintype "passive"))
      (node (ref "U2") (pin "1") (pinfunction "BOOT_1") (pintype "input"))
    )
    (net (code "53") (name "Net-(U2-COMP)") (class "Default")
      (node (ref "C3") (pin "2") (pinfunction "2_2") (pintype "passive"))
      (node (ref "R2") (pin "1") (pinfunction "1_1") (pintype "passive"))
      (node (ref "U2") (pin "6") (pinfunction "COMP_6") (pintype "input"))
    )
    (net (code "54") (name "Net-(U2-FB)") (class "Default")
      (node (ref "D2") (pin "C") (pinfunction "C_C") (pintype "passive"))
      (node (ref "R15") (pin "1") (pinfunction "1_1") (pintype "passive"))
      (node (ref "U2") (pin "5") (pinfunction "FB_5") (pintype "input"))
    )
    (net (code "55") (name "Net-(U2-RT{slash}CL)") (class "Default")
      (node (ref "R1") (pin "2") (pinfunction "2_2") (pintype "passive"))
      (node (ref "U2") (pin "4") (pinfunction "RT/CL_4") (pintype "input"))
    )
    (net (code "56") (name "Net-(U3-IN-)") (class "Default")
      (node (ref "R34") (pin "2") (pinfunction "2_2") (pintype "passive"))
      (node (ref "U3") (pin "5") (pinfunction "IN-_5") (pintype "input"))
    )
    (net (code "57") (name "Net-(U3-OUT)") (class "Default")
      (node (ref "R12") (pin "1") (pinfunction "1_1") (pintype "passive"))
      (node (ref "U3") (pin "6") (pinfunction "OUT_6") (pintype "output"))
    )
    (net (code "58") (name "Net-(U4-C)") (class "Default")
      (node (ref "C17") (pin "2") (pinfunction "2_2") (pintype "passive"))
      (node (ref "R22") (pin "2") (pinfunction "2_2") (pintype "passive"))
      (node (ref "R26") (pin "2") (pinfunction "2_2") (pintype "passive"))
      (node (ref "U4") (pin "1") (pinfunction "C_1") (pintype "passive"))
      (node (ref "U4") (pin "2") (pinfunction "R_2") (pintype "passive"))
    )
    (net (code "59") (name "Net-(U5-R)") (class "Default")
      (node (ref "R30") (pin "2") (pinfunction "2_2") (pintype "passive"))
      (node (ref "R31") (pin "1") (pinfunction "1_1") (pintype "passive"))
      (node (ref "U5") (pin "2") (pinfunction "R_2") (pintype "passive"))
    )
    (net (code "60") (name "Net-(X1A-KL)") (class "Default")
      (node (ref "R28") (pin "2") (pinfunction "2_2") (pintype "passive"))
      (node (ref "R29") (pin "1") (pinfunction "1_1") (pintype "passive"))
      (node (ref "X1") (pin "1") (pinfunction "KL_1") (pintype "passive"))
    )
    (net (code "61") (name "Net-(X1B-KL)") (class "Default")
      (node (ref "R40") (pin "2") (pinfunction "2_2") (pintype "passive"))
      (node (ref "X1") (pin "2") (pinfunction "KL_2") (pintype "passive"))
    )
    (net (code "62") (name "Net-(X1C-KL)") (class "Default")
      (node (ref "R12") (pin "2") (pinfunction "2_2") (pintype "passive"))
      (node (ref "X1") (pin "3") (pinfunction "KL_3") (pintype "passive"))
    )
    (net (code "63") (name "Net-(X1D-KL)") (class "Default")
      (node (ref "R18") (pin "2") (pinfunction "2_2") (pintype "passive"))
      (node (ref "X1") (pin "4") (pinfunction "KL_4") (pintype "passive"))
    )
    (net (code "64") (name "OUT+") (class "Default")
      (node (ref "C19") (pin "1") (pinfunction "1_1") (pintype "passive"))
      (node (ref "C20") (pin "1") (pinfunction "1_1") (pintype "passive"))
      (node (ref "D6") (pin "C") (pinfunction "C_C") (pintype "passive"))
      (node (ref "D9") (pin "C") (pinfunction "C_C") (pintype "passive"))
      (node (ref "JP1") (pin "1") (pinfunction "1_1") (pintype "passive"))
      (node (ref "JP1") (pin "2") (pinfunction "2_2") (pintype "passive"))
      (node (ref "R3") (pin "2") (pinfunction "2_2") (pintype "passive"))
      (node (ref "R51") (pin "2") (pinfunction "2_2") (pintype "passive"))
      (node (ref "T2") (pin "3") (pinfunction "S_3") (pintype "passive"))
      (node (ref "T3") (pin "2") (pinfunction "D_2") (pintype "passive"))
      (node (ref "X2") (pin "1") (pinfunction "KL_1") (pintype "passive"))
      (node (ref "X5") (pin "2") (pinfunction "S_2") (pintype "passive"))
    )
    (net (code "65") (name "V+") (class "Default")
      (node (ref "C20") (pin "2") (pinfunction "2_2") (pintype "passive"))
      (node (ref "OK1") (pin "4") (pinfunction "COL_4") (pintype "passive"))
      (node (ref "OK2") (pin "4") (pinfunction "COL_4") (pintype "passive"))
      (node (ref "OK4") (pin "4") (pinfunction "COL_4") (pintype "passive"))
      (node (ref "X5") (pin "1") (pinfunction "S_1") (pintype "passive"))
    )
    (net (code "66") (name "unconnected-(IC1B-OUT-Pad7)") (class "Default")
      (node (ref "IC1") (pin "7") (pinfunction "OUT_7") (pintype "output"))
    )
    (net (code "67") (name "unconnected-(IC2B-OUT-Pad7)") (class "Default")
      (node (ref "IC2") (pin "7") (pinfunction "OUT_7") (pintype "output"))
    )
    (net (code "68") (name "unconnected-(U2-EN-Pad3)") (class "Default")
      (node (ref "U2") (pin "3") (pinfunction "EN_3") (pintype "input"))
    )
  )
)
